# CPU_Stop.net
KiCad netlist of a schematic drawn in EAGLE
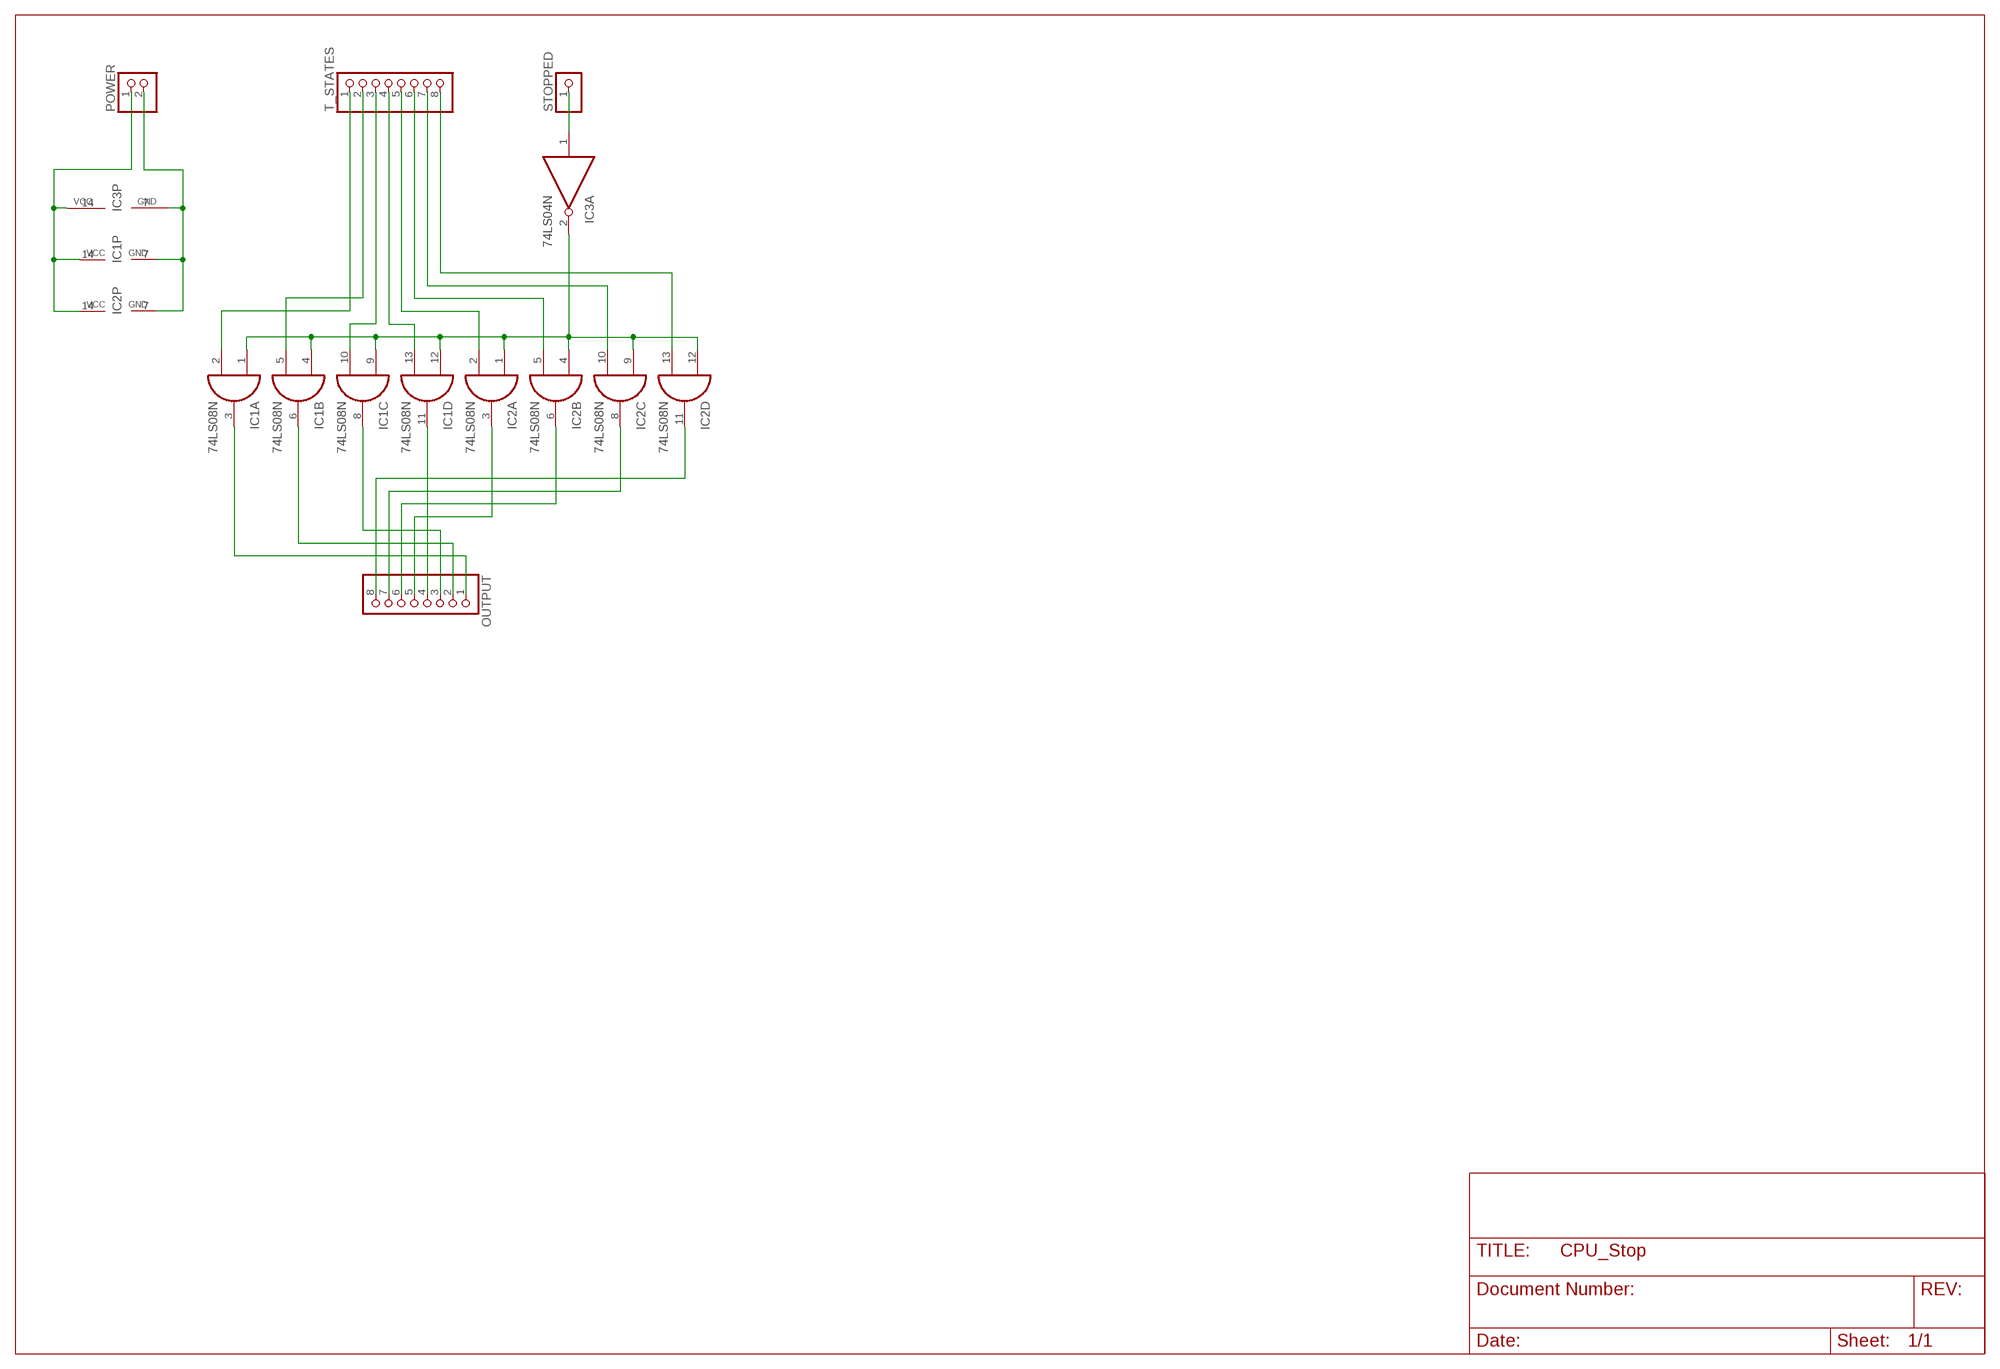
[diagram p0: schematic, sheet 1]

(export (version "E")
  (design (tool "Eeschema 10.0.6"))
  (components
    (comp (ref "IC1")
      (value "74LS08N")
      (footprint "eagle-import:DIL14")
      (libsource (lib "eagle-import") (part "7408NLS"))
    )
    (comp (ref "IC2")
      (value "74LS08N")
      (footprint "eagle-import:DIL14")
      (libsource (lib "eagle-import") (part "7408NLS"))
    )
    (comp (ref "IC3")
      (value "74LS04N")
      (footprint "eagle-import:DIL14")
      (libsource (lib "eagle-import") (part "7404NLS"))
    )
    (comp (ref "OUTPUT")
      (value "PINHD-1X8")
      (footprint "eagle-import:1X08")
      (libsource (lib "eagle-import") (part "PINHD-1X8"))
    )
    (comp (ref "POWER")
      (value "PINHD-1X2")
      (footprint "eagle-import:1X02")
      (libsource (lib "eagle-import") (part "PINHD-1X2"))
    )
    (comp (ref "STOPPED")
      (value "PINHD-1X1")
      (footprint "eagle-import:1X01")
      (libsource (lib "eagle-import") (part "PINHD-1X1"))
    )
    (comp (ref "T_STATES")
      (value "PINHD-1X8")
      (footprint "eagle-import:1X08")
      (libsource (lib "eagle-import") (part "PINHD-1X8"))
    )
  )
  (nets
    (net (code "1") (name "Net-(IC1A-I0)") (class "Default")
      (node (ref "IC1") (pin "1") (pinfunction "I0_1") (pintype "input"))
      (node (ref "IC1") (pin "12") (pinfunction "I0_12") (pintype "input"))
      (node (ref "IC1") (pin "4") (pinfunction "I0_4") (pintype "input"))
      (node (ref "IC1") (pin "9") (pinfunction "I0_9") (pintype "input"))
      (node (ref "IC2") (pin "1") (pinfunction "I0_1") (pintype "input"))
      (node (ref "IC2") (pin "12") (pinfunction "I0_12") (pintype "input"))
      (node (ref "IC2") (pin "4") (pinfunction "I0_4") (pintype "input"))
      (node (ref "IC2") (pin "9") (pinfunction "I0_9") (pintype "input"))
      (node (ref "IC3") (pin "2") (pinfunction "O_2") (pintype "output"))
    )
    (net (code "2") (name "Net-(IC1A-I1)") (class "Default")
      (node (ref "IC1") (pin "2") (pinfunction "I1_2") (pintype "input"))
      (node (ref "T_STATES") (pin "1") (pinfunction "1_1") (pintype "passive"))
    )
    (net (code "3") (name "Net-(IC1A-O)") (class "Default")
      (node (ref "IC1") (pin "3") (pinfunction "O_3") (pintype "output"))
      (node (ref "OUTPUT") (pin "1") (pinfunction "1_1") (pintype "passive"))
    )
    (net (code "4") (name "Net-(IC1B-I1)") (class "Default")
      (node (ref "IC1") (pin "5") (pinfunction "I1_5") (pintype "input"))
      (node (ref "T_STATES") (pin "2") (pinfunction "2_2") (pintype "passive"))
    )
    (net (code "5") (name "Net-(IC1B-O)") (class "Default")
      (node (ref "IC1") (pin "6") (pinfunction "O_6") (pintype "output"))
      (node (ref "OUTPUT") (pin "2") (pinfunction "2_2") (pintype "passive"))
    )
    (net (code "6") (name "Net-(IC1C-I1)") (class "Default")
      (node (ref "IC1") (pin "10") (pinfunction "I1_10") (pintype "input"))
      (node (ref "T_STATES") (pin "3") (pinfunction "3_3") (pintype "passive"))
    )
    (net (code "7") (name "Net-(IC1C-O)") (class "Default")
      (node (ref "IC1") (pin "8") (pinfunction "O_8") (pintype "output"))
      (node (ref "OUTPUT") (pin "3") (pinfunction "3_3") (pintype "passive"))
    )
    (net (code "8") (name "Net-(IC1D-I1)") (class "Default")
      (node (ref "IC1") (pin "13") (pinfunction "I1_13") (pintype "input"))
      (node (ref "T_STATES") (pin "4") (pinfunction "4_4") (pintype "passive"))
    )
    (net (code "9") (name "Net-(IC1D-O)") (class "Default")
      (node (ref "IC1") (pin "11") (pinfunction "O_11") (pintype "output"))
      (node (ref "OUTPUT") (pin "4") (pinfunction "4_4") (pintype "passive"))
    )
    (net (code "10") (name "Net-(IC1E-GND)") (class "Default")
      (node (ref "IC1") (pin "7") (pinfunction "GND_7") (pintype "power_in"))
      (node (ref "IC2") (pin "7") (pinfunction "GND_7") (pintype "power_in"))
      (node (ref "IC3") (pin "7") (pinfunction "GND_7") (pintype "power_in"))
      (node (ref "POWER") (pin "2") (pinfunction "2_2") (pintype "passive"))
    )
    (net (code "11") (name "Net-(IC1E-VCC)") (class "Default")
      (node (ref "IC1") (pin "14") (pinfunction "VCC_14") (pintype "power_in"))
      (node (ref "IC2") (pin "14") (pinfunction "VCC_14") (pintype "power_in"))
      (node (ref "IC3") (pin "14") (pinfunction "VCC_14") (pintype "power_in"))
      (node (ref "POWER") (pin "1") (pinfunction "1_1") (pintype "passive"))
    )
    (net (code "12") (name "Net-(IC2A-I1)") (class "Default")
      (node (ref "IC2") (pin "2") (pinfunction "I1_2") (pintype "input"))
      (node (ref "T_STATES") (pin "5") (pinfunction "5_5") (pintype "passive"))
    )
    (net (code "13") (name "Net-(IC2A-O)") (class "Default")
      (node (ref "IC2") (pin "3") (pinfunction "O_3") (pintype "output"))
      (node (ref "OUTPUT") (pin "5") (pinfunction "5_5") (pintype "passive"))
    )
    (net (code "14") (name "Net-(IC2B-I1)") (class "Default")
      (node (ref "IC2") (pin "5") (pinfunction "I1_5") (pintype "input"))
      (node (ref "T_STATES") (pin "6") (pinfunction "6_6") (pintype "passive"))
    )
    (net (code "15") (name "Net-(IC2B-O)") (class "Default")
      (node (ref "IC2") (pin "6") (pinfunction "O_6") (pintype "output"))
      (node (ref "OUTPUT") (pin "6") (pinfunction "6_6") (pintype "passive"))
    )
    (net (code "16") (name "Net-(IC2C-I1)") (class "Default")
      (node (ref "IC2") (pin "10") (pinfunction "I1_10") (pintype "input"))
      (node (ref "T_STATES") (pin "7") (pinfunction "7_7") (pintype "passive"))
    )
    (net (code "17") (name "Net-(IC2C-O)") (class "Default")
      (node (ref "IC2") (pin "8") (pinfunction "O_8") (pintype "output"))
      (node (ref "OUTPUT") (pin "7") (pinfunction "7_7") (pintype "passive"))
    )
    (net (code "18") (name "Net-(IC2D-I1)") (class "Default")
      (node (ref "IC2") (pin "13") (pinfunction "I1_13") (pintype "input"))
      (node (ref "T_STATES") (pin "8") (pinfunction "8_8") (pintype "passive"))
    )
    (net (code "19") (name "Net-(IC2D-O)") (class "Default")
      (node (ref "IC2") (pin "11") (pinfunction "O_11") (pintype "output"))
      (node (ref "OUTPUT") (pin "8") (pinfunction "8_8") (pintype "passive"))
    )
    (net (code "20") (name "Net-(IC3A-I)") (class "Default")
      (node (ref "IC3") (pin "1") (pinfunction "I_1") (pintype "input"))
      (node (ref "STOPPED") (pin "1") (pinfunction "1_1") (pintype "passive"))
    )
  )
)
